# USB-C_Connectors.net
KiCad netlist of a schematic drawn in Altium Designer
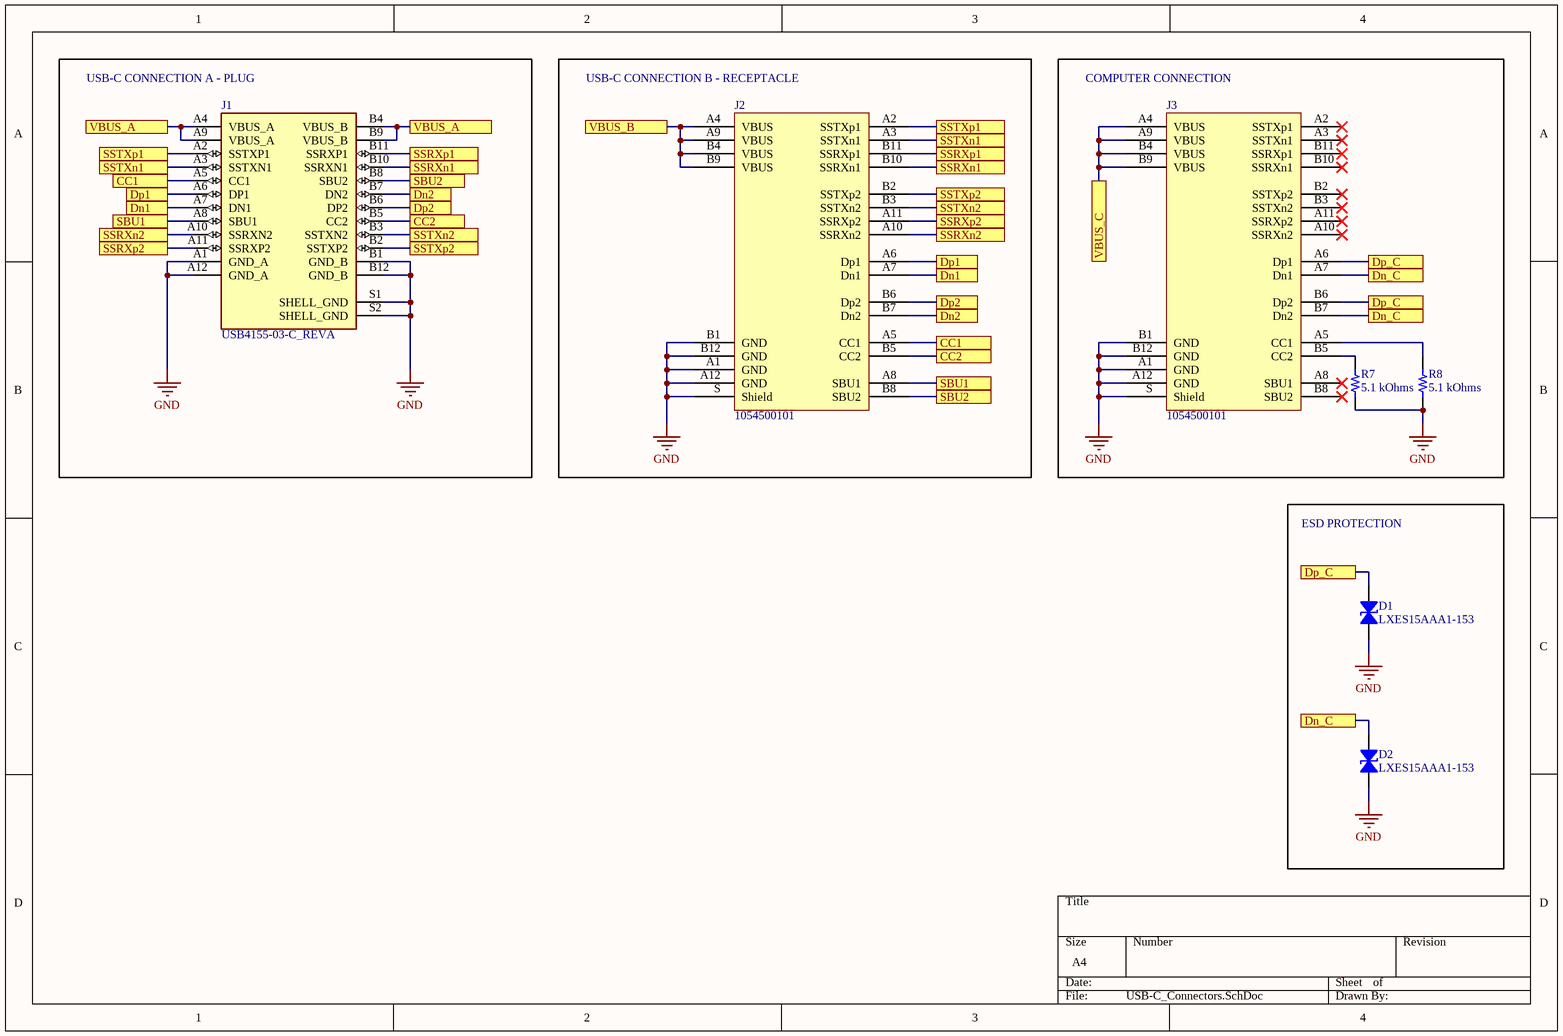
[diagram p0: USB-C_Connectors.SchDoc]

(export (version "E")
  (design (tool "Eeschema 10.0.6"))
  (components
    (comp (ref "D1")
      (value "LXES15AAA1-153")
      (footprint "0402")
      (description "TVS DIODE 4V 1005")
      (fields (field (name "MANUFACTURER") "Murata Electronics"))
      (libsource (lib "Celestial Altium Library - altium_library") (part "Diode TVS"))
    )
    (comp (ref "D2")
      (value "LXES15AAA1-153")
      (footprint "0402")
      (description "TVS DIODE 4V 1005")
      (fields (field (name "MANUFACTURER") "Murata Electronics"))
      (libsource (lib "Celestial Altium Library - altium_library") (part "Diode TVS"))
    )
    (comp (ref "J1")
      (value "USB4155-03-C_REVA")
      (footprint "USB4155-03-C:GCT_USB4155-03-C_REVA")
      (fields (field (name "MF") "{'manufacturer': u'Global Connector Technology'}"))
      (libsource (lib "*") (part "USB4155-03-C_REVA"))
    )
    (comp (ref "J2")
      (value "1054500101")
      (footprint "Molex 1054500101")
      (description "CONN RCP USB3.1 TYPEC 24P SMD RA")
      (fields (field (name "MANUFACTURER") "Molex"))
      (libsource (lib "Celestial Altium Library - altium_library") (part "USB 3.0 Type C"))
    )
    (comp (ref "J3")
      (value "1054500101")
      (footprint "Molex 1054500101")
      (description "CONN RCP USB3.1 TYPEC 24P SMD RA")
      (fields (field (name "MANUFACTURER") "Molex"))
      (libsource (lib "Celestial Altium Library - altium_library") (part "USB 3.0 Type C"))
    )
    (comp (ref "R7")
      (value "5.1 kOhms")
      (footprint "RES 0603_1608")
      (description "RES 5.1K OHM 5% 1/10W 0603")
      (fields
        (field (name "PART NUMBER") "RK73B1JTTD512J")
        (field (name "MANUFACTURER") "KOA Speer Electronics, Inc.")
      )
      (libsource (lib "Celestial Altium Library - altium_library") (part "Resistor"))
    )
    (comp (ref "R8")
      (value "5.1 kOhms")
      (footprint "RES 0603_1608")
      (description "RES 5.1K OHM 5% 1/10W 0603")
      (fields
        (field (name "PART NUMBER") "RK73B1JTTD512J")
        (field (name "MANUFACTURER") "KOA Speer Electronics, Inc.")
      )
      (libsource (lib "Celestial Altium Library - altium_library") (part "Resistor"))
    )
  )
  (nets
    (net (code "1") (name "/CC1") (class "Default")
      (node (ref "J1") (pin "A5") (pinfunction "CC1_A5") (pintype "bidirectional"))
      (node (ref "J2") (pin "A5") (pinfunction "CC1_A5") (pintype "passive"))
    )
    (net (code "2") (name "/CC2") (class "Default")
      (node (ref "J1") (pin "B5") (pinfunction "CC2_B5") (pintype "bidirectional"))
      (node (ref "J2") (pin "B5") (pinfunction "CC2_B5") (pintype "passive"))
    )
    (net (code "3") (name "/Dn1") (class "Default")
      (node (ref "J1") (pin "A7") (pinfunction "DN1_A7") (pintype "bidirectional"))
      (node (ref "J2") (pin "A7") (pinfunction "Dn1_A7") (pintype "passive"))
    )
    (net (code "4") (name "/Dn2") (class "Default")
      (node (ref "J1") (pin "B7") (pinfunction "DN2_B7") (pintype "bidirectional"))
      (node (ref "J2") (pin "B7") (pinfunction "Dn2_B7") (pintype "passive"))
    )
    (net (code "5") (name "/Dn_C") (class "Default")
      (node (ref "D2") (pin "1") (pinfunction "1_1") (pintype "passive"))
      (node (ref "J3") (pin "A7") (pinfunction "Dn1_A7") (pintype "passive"))
      (node (ref "J3") (pin "B7") (pinfunction "Dn2_B7") (pintype "passive"))
    )
    (net (code "6") (name "/Dp1") (class "Default")
      (node (ref "J1") (pin "A6") (pinfunction "DP1_A6") (pintype "bidirectional"))
      (node (ref "J2") (pin "A6") (pinfunction "Dp1_A6") (pintype "passive"))
    )
    (net (code "7") (name "/Dp2") (class "Default")
      (node (ref "J1") (pin "B6") (pinfunction "DP2_B6") (pintype "bidirectional"))
      (node (ref "J2") (pin "B6") (pinfunction "Dp2_B6") (pintype "passive"))
    )
    (net (code "8") (name "/Dp_C") (class "Default")
      (node (ref "D1") (pin "1") (pinfunction "1_1") (pintype "passive"))
      (node (ref "J3") (pin "A6") (pinfunction "Dp1_A6") (pintype "passive"))
      (node (ref "J3") (pin "B6") (pinfunction "Dp2_B6") (pintype "passive"))
    )
    (net (code "9") (name "/SBU1") (class "Default")
      (node (ref "J1") (pin "A8") (pinfunction "SBU1_A8") (pintype "bidirectional"))
      (node (ref "J2") (pin "A8") (pinfunction "SBU1_A8") (pintype "passive"))
    )
    (net (code "10") (name "/SBU2") (class "Default")
      (node (ref "J1") (pin "B8") (pinfunction "SBU2_B8") (pintype "bidirectional"))
      (node (ref "J2") (pin "B8") (pinfunction "SBU2_B8") (pintype "passive"))
    )
    (net (code "11") (name "/SSRXn1") (class "Default")
      (node (ref "J1") (pin "B10") (pinfunction "SSRXN1_B10") (pintype "bidirectional"))
      (node (ref "J2") (pin "B10") (pinfunction "SSRXn1_B10") (pintype "passive"))
    )
    (net (code "12") (name "/SSRXn2") (class "Default")
      (node (ref "J1") (pin "A10") (pinfunction "SSRXN2_A10") (pintype "bidirectional"))
      (node (ref "J2") (pin "A10") (pinfunction "SSRXn2_A10") (pintype "passive"))
    )
    (net (code "13") (name "/SSRXp1") (class "Default")
      (node (ref "J1") (pin "B11") (pinfunction "SSRXP1_B11") (pintype "bidirectional"))
      (node (ref "J2") (pin "B11") (pinfunction "SSRXp1_B11") (pintype "passive"))
    )
    (net (code "14") (name "/SSRXp2") (class "Default")
      (node (ref "J1") (pin "A11") (pinfunction "SSRXP2_A11") (pintype "bidirectional"))
      (node (ref "J2") (pin "A11") (pinfunction "SSRXp2_A11") (pintype "passive"))
    )
    (net (code "15") (name "/SSTXn1") (class "Default")
      (node (ref "J1") (pin "A3") (pinfunction "SSTXN1_A3") (pintype "bidirectional"))
      (node (ref "J2") (pin "A3") (pinfunction "SSTXn1_A3") (pintype "passive"))
    )
    (net (code "16") (name "/SSTXn2") (class "Default")
      (node (ref "J1") (pin "B3") (pinfunction "SSTXN2_B3") (pintype "bidirectional"))
      (node (ref "J2") (pin "B3") (pinfunction "SSTXn2_B3") (pintype "passive"))
    )
    (net (code "17") (name "/SSTXp1") (class "Default")
      (node (ref "J1") (pin "A2") (pinfunction "SSTXP1_A2") (pintype "bidirectional"))
      (node (ref "J2") (pin "A2") (pinfunction "SSTXp1_A2") (pintype "passive"))
    )
    (net (code "18") (name "/SSTXp2") (class "Default")
      (node (ref "J1") (pin "B2") (pinfunction "SSTXP2_B2") (pintype "bidirectional"))
      (node (ref "J2") (pin "B2") (pinfunction "SSTXp2_B2") (pintype "passive"))
    )
    (net (code "19") (name "/VBUS_A") (class "Default")
      (node (ref "J1") (pin "A4") (pinfunction "VBUS_A_A4") (pintype "power_in"))
      (node (ref "J1") (pin "A9") (pinfunction "VBUS_A_A9") (pintype "power_in"))
      (node (ref "J1") (pin "B4") (pinfunction "VBUS_B_B4") (pintype "power_in"))
      (node (ref "J1") (pin "B9") (pinfunction "VBUS_B_B9") (pintype "power_in"))
    )
    (net (code "20") (name "/VBUS_B") (class "Default")
      (node (ref "J2") (pin "A4") (pinfunction "VBUS_A4") (pintype "passive"))
      (node (ref "J2") (pin "A9") (pinfunction "VBUS_A9") (pintype "passive"))
      (node (ref "J2") (pin "B4") (pinfunction "VBUS_B4") (pintype "passive"))
      (node (ref "J2") (pin "B9") (pinfunction "VBUS_B9") (pintype "passive"))
    )
    (net (code "21") (name "/VBUS_C") (class "Default")
      (node (ref "J3") (pin "A4") (pinfunction "VBUS_A4") (pintype "passive"))
      (node (ref "J3") (pin "A9") (pinfunction "VBUS_A9") (pintype "passive"))
      (node (ref "J3") (pin "B4") (pinfunction "VBUS_B4") (pintype "passive"))
      (node (ref "J3") (pin "B9") (pinfunction "VBUS_B9") (pintype "passive"))
    )
    (net (code "22") (name "GND") (class "Default")
      (node (ref "D1") (pin "2") (pinfunction "2_2") (pintype "passive"))
      (node (ref "D2") (pin "2") (pinfunction "2_2") (pintype "passive"))
      (node (ref "J1") (pin "A1") (pinfunction "GND_A_A1") (pintype "power_in"))
      (node (ref "J1") (pin "A12") (pinfunction "GND_A_A12") (pintype "power_in"))
      (node (ref "J1") (pin "B1") (pinfunction "GND_B_B1") (pintype "power_in"))
      (node (ref "J1") (pin "B12") (pinfunction "GND_B_B12") (pintype "power_in"))
      (node (ref "J1") (pin "S1") (pinfunction "SHELL_GND_S1") (pintype "power_in"))
      (node (ref "J1") (pin "S2") (pinfunction "SHELL_GND_S2") (pintype "power_in"))
      (node (ref "J2") (pin "A1") (pinfunction "GND_A1") (pintype "passive"))
      (node (ref "J2") (pin "A12") (pinfunction "GND_A12") (pintype "passive"))
      (node (ref "J2") (pin "B1") (pinfunction "GND_B1") (pintype "passive"))
      (node (ref "J2") (pin "B12") (pinfunction "GND_B12") (pintype "passive"))
      (node (ref "J2") (pin "S") (pinfunction "Shield_S") (pintype "passive"))
      (node (ref "J3") (pin "A1") (pinfunction "GND_A1") (pintype "passive"))
      (node (ref "J3") (pin "A12") (pinfunction "GND_A12") (pintype "passive"))
      (node (ref "J3") (pin "B1") (pinfunction "GND_B1") (pintype "passive"))
      (node (ref "J3") (pin "B12") (pinfunction "GND_B12") (pintype "passive"))
      (node (ref "J3") (pin "S") (pinfunction "Shield_S") (pintype "passive"))
      (node (ref "R7") (pin "1") (pinfunction "1_1") (pintype "passive"))
      (node (ref "R8") (pin "2") (pinfunction "2_2") (pintype "passive"))
    )
    (net (code "23") (name "Net-(J3-CC1)") (class "Default")
      (node (ref "J3") (pin "A5") (pinfunction "CC1_A5") (pintype "passive"))
      (node (ref "R8") (pin "1") (pinfunction "1_1") (pintype "passive"))
    )
    (net (code "24") (name "Net-(J3-CC2)") (class "Default")
      (node (ref "J3") (pin "B5") (pinfunction "CC2_B5") (pintype "passive"))
      (node (ref "R7") (pin "2") (pinfunction "2_2") (pintype "passive"))
    )
    (net (code "25") (name "unconnected-(J3-SBU1-PadA8)") (class "Default")
      (node (ref "J3") (pin "A8") (pinfunction "SBU1_A8") (pintype "passive+no_connect"))
    )
    (net (code "26") (name "unconnected-(J3-SBU2-PadB8)") (class "Default")
      (node (ref "J3") (pin "B8") (pinfunction "SBU2_B8") (pintype "passive+no_connect"))
    )
    (net (code "27") (name "unconnected-(J3-SSRXn1-PadB10)") (class "Default")
      (node (ref "J3") (pin "B10") (pinfunction "SSRXn1_B10") (pintype "passive+no_connect"))
    )
    (net (code "28") (name "unconnected-(J3-SSRXn2-PadA10)") (class "Default")
      (node (ref "J3") (pin "A10") (pinfunction "SSRXn2_A10") (pintype "passive+no_connect"))
    )
    (net (code "29") (name "unconnected-(J3-SSRXp1-PadB11)") (class "Default")
      (node (ref "J3") (pin "B11") (pinfunction "SSRXp1_B11") (pintype "passive+no_connect"))
    )
    (net (code "30") (name "unconnected-(J3-SSRXp2-PadA11)") (class "Default")
      (node (ref "J3") (pin "A11") (pinfunction "SSRXp2_A11") (pintype "passive+no_connect"))
    )
    (net (code "31") (name "unconnected-(J3-SSTXn1-PadA3)") (class "Default")
      (node (ref "J3") (pin "A3") (pinfunction "SSTXn1_A3") (pintype "passive+no_connect"))
    )
    (net (code "32") (name "unconnected-(J3-SSTXn2-PadB3)") (class "Default")
      (node (ref "J3") (pin "B3") (pinfunction "SSTXn2_B3") (pintype "passive+no_connect"))
    )
    (net (code "33") (name "unconnected-(J3-SSTXp1-PadA2)") (class "Default")
      (node (ref "J3") (pin "A2") (pinfunction "SSTXp1_A2") (pintype "passive+no_connect"))
    )
    (net (code "34") (name "unconnected-(J3-SSTXp2-PadB2)") (class "Default")
      (node (ref "J3") (pin "B2") (pinfunction "SSTXp2_B2") (pintype "passive+no_connect"))
    )
  )
)
